# BSPD_Tester.net
KiCad netlist of a schematic drawn in EAGLE
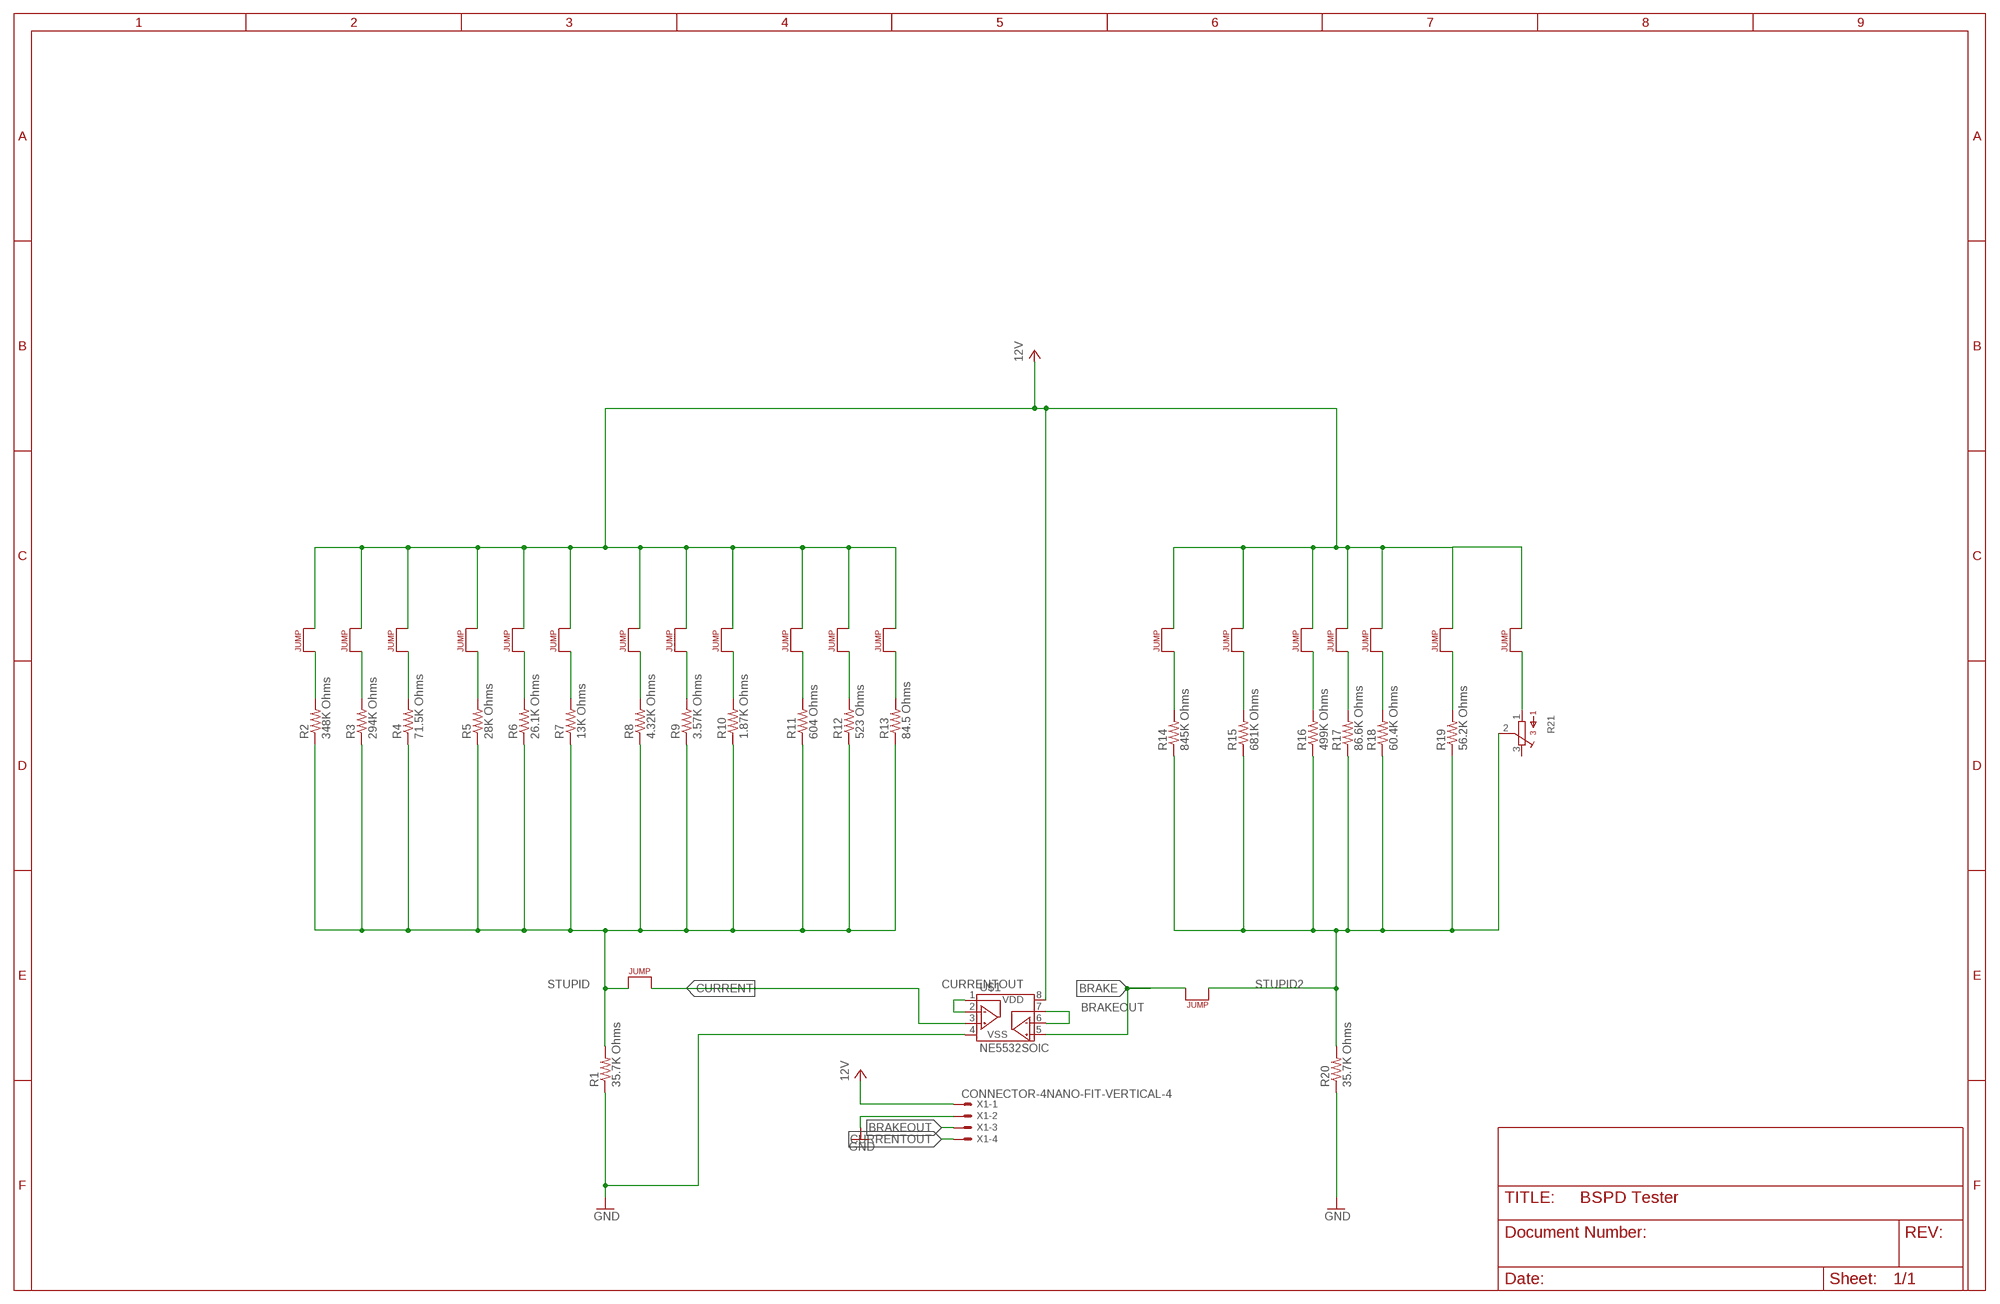
[diagram p0: schematic, sheet 1]

(export (version "E")
  (design (tool "Eeschema 10.0.6"))
  (components
    (comp (ref "J1")
      (value "JUMPER.1")
      (footprint "eagle-import:1X02")
      (libsource (lib "eagle-import") (part "JUMPER.1"))
    )
    (comp (ref "J2")
      (value "JUMPER.1")
      (footprint "eagle-import:1X02")
      (libsource (lib "eagle-import") (part "JUMPER.1"))
    )
    (comp (ref "J3")
      (value "JUMPER.1")
      (footprint "eagle-import:1X02")
      (libsource (lib "eagle-import") (part "JUMPER.1"))
    )
    (comp (ref "J4")
      (value "JUMPER.1")
      (footprint "eagle-import:1X02")
      (libsource (lib "eagle-import") (part "JUMPER.1"))
    )
    (comp (ref "J5")
      (value "JUMPER.1")
      (footprint "eagle-import:1X02")
      (libsource (lib "eagle-import") (part "JUMPER.1"))
    )
    (comp (ref "J6")
      (value "JUMPER.1")
      (footprint "eagle-import:1X02")
      (libsource (lib "eagle-import") (part "JUMPER.1"))
    )
    (comp (ref "J7")
      (value "JUMPER.1")
      (footprint "eagle-import:1X02")
      (libsource (lib "eagle-import") (part "JUMPER.1"))
    )
    (comp (ref "J8")
      (value "JUMPER.1")
      (footprint "eagle-import:1X02")
      (libsource (lib "eagle-import") (part "JUMPER.1"))
    )
    (comp (ref "J9")
      (value "JUMPER.1")
      (footprint "eagle-import:1X02")
      (libsource (lib "eagle-import") (part "JUMPER.1"))
    )
    (comp (ref "J10")
      (value "JUMPER.1")
      (footprint "eagle-import:1X02")
      (libsource (lib "eagle-import") (part "JUMPER.1"))
    )
    (comp (ref "J11")
      (value "JUMPER.1")
      (footprint "eagle-import:1X02")
      (libsource (lib "eagle-import") (part "JUMPER.1"))
    )
    (comp (ref "J12")
      (value "JUMPER.1")
      (footprint "eagle-import:1X02")
      (libsource (lib "eagle-import") (part "JUMPER.1"))
    )
    (comp (ref "J13")
      (value "JUMPER.1")
      (footprint "eagle-import:1X02")
      (libsource (lib "eagle-import") (part "JUMPER.1"))
    )
    (comp (ref "J14")
      (value "JUMPER.1")
      (footprint "eagle-import:1X02")
      (libsource (lib "eagle-import") (part "JUMPER.1"))
    )
    (comp (ref "J15")
      (value "JUMPER.1")
      (footprint "eagle-import:1X02")
      (libsource (lib "eagle-import") (part "JUMPER.1"))
    )
    (comp (ref "J16")
      (value "JUMPER.1")
      (footprint "eagle-import:1X02")
      (libsource (lib "eagle-import") (part "JUMPER.1"))
    )
    (comp (ref "J17")
      (value "JUMPER.1")
      (footprint "eagle-import:1X02")
      (libsource (lib "eagle-import") (part "JUMPER.1"))
    )
    (comp (ref "J18")
      (value "JUMPER.1")
      (footprint "eagle-import:1X02")
      (libsource (lib "eagle-import") (part "JUMPER.1"))
    )
    (comp (ref "J19")
      (value "JUMPER.1")
      (footprint "eagle-import:1X02")
      (libsource (lib "eagle-import") (part "JUMPER.1"))
    )
    (comp (ref "J20")
      (value "JUMPER.1")
      (footprint "eagle-import:1X02")
      (libsource (lib "eagle-import") (part "JUMPER.1"))
    )
    (comp (ref "J21")
      (value "JUMPER.1")
      (footprint "eagle-import:1X02")
      (libsource (lib "eagle-import") (part "JUMPER.1"))
    )
    (comp (ref "R1")
      (value "35.7K Ohms")
      (footprint "eagle-import:1206")
      (libsource (lib "eagle-import") (part "RESISTOR1206"))
    )
    (comp (ref "R2")
      (value "348K Ohms")
      (footprint "eagle-import:1206")
      (libsource (lib "eagle-import") (part "RESISTOR1206"))
    )
    (comp (ref "R3")
      (value "294K Ohms")
      (footprint "eagle-import:1206")
      (libsource (lib "eagle-import") (part "RESISTOR1206"))
    )
    (comp (ref "R4")
      (value "71.5K Ohms")
      (footprint "eagle-import:1206")
      (libsource (lib "eagle-import") (part "RESISTOR1206"))
    )
    (comp (ref "R5")
      (value "28K Ohms")
      (footprint "eagle-import:1206")
      (libsource (lib "eagle-import") (part "RESISTOR1206"))
    )
    (comp (ref "R6")
      (value "26.1K Ohms")
      (footprint "eagle-import:1206")
      (libsource (lib "eagle-import") (part "RESISTOR1206"))
    )
    (comp (ref "R7")
      (value "13K Ohms")
      (footprint "eagle-import:1206")
      (libsource (lib "eagle-import") (part "RESISTOR1206"))
    )
    (comp (ref "R8")
      (value "4.32K Ohms")
      (footprint "eagle-import:1206")
      (libsource (lib "eagle-import") (part "RESISTOR1206"))
    )
    (comp (ref "R9")
      (value "3.57K Ohms")
      (footprint "eagle-import:1206")
      (libsource (lib "eagle-import") (part "RESISTOR1206"))
    )
    (comp (ref "R10")
      (value "1.87K Ohms")
      (footprint "eagle-import:1206")
      (libsource (lib "eagle-import") (part "RESISTOR1206"))
    )
    (comp (ref "R11")
      (value "604 Ohms")
      (footprint "eagle-import:1206")
      (libsource (lib "eagle-import") (part "RESISTOR1206"))
    )
    (comp (ref "R12")
      (value "523 Ohms")
      (footprint "eagle-import:1206")
      (libsource (lib "eagle-import") (part "RESISTOR1206"))
    )
    (comp (ref "R13")
      (value "84.5 Ohms")
      (footprint "eagle-import:1206")
      (libsource (lib "eagle-import") (part "RESISTOR1206"))
    )
    (comp (ref "R14")
      (value "845K Ohms")
      (footprint "eagle-import:1206")
      (libsource (lib "eagle-import") (part "RESISTOR1206"))
    )
    (comp (ref "R15")
      (value "681K Ohms")
      (footprint "eagle-import:1206")
      (libsource (lib "eagle-import") (part "RESISTOR1206"))
    )
    (comp (ref "R16")
      (value "499K Ohms")
      (footprint "eagle-import:1206")
      (libsource (lib "eagle-import") (part "RESISTOR1206"))
    )
    (comp (ref "R17")
      (value "86.6K Ohms")
      (footprint "eagle-import:1206")
      (libsource (lib "eagle-import") (part "RESISTOR1206"))
    )
    (comp (ref "R18")
      (value "60.4K Ohms")
      (footprint "eagle-import:1206")
      (libsource (lib "eagle-import") (part "RESISTOR1206"))
    )
    (comp (ref "R19")
      (value "56.2K Ohms")
      (footprint "eagle-import:1206")
      (libsource (lib "eagle-import") (part "RESISTOR1206"))
    )
    (comp (ref "R20")
      (value "35.7K Ohms")
      (footprint "eagle-import:1206")
      (libsource (lib "eagle-import") (part "RESISTOR1206"))
    )
    (comp (ref "R21")
      (value "TRIMPOT_3296C")
      (footprint "eagle-import:TRIMPOT_3296")
      (libsource (lib "eagle-import") (part "TRIMPOT_3296C"))
    )
    (comp (ref "U$1")
      (value "NE5532SOIC")
      (footprint "eagle-import:SOIC-08")
      (libsource (lib "eagle-import") (part "NE5532SOIC"))
    )
    (comp (ref "X1")
      (value "CONNECTOR-4NANO-FIT-VERTICAL-4")
      (footprint "eagle-import:NANO-FIT_VERTICAL-4")
      (libsource (lib "eagle-import") (part "CONNECTOR-4NANO-FIT-VERTICAL-4"))
    )
  )
  (nets
    (net (code "1") (name "/STUPID") (class "Default")
      (node (ref "J19") (pin "1") (pinfunction "P$1_1") (pintype "bidirectional"))
      (node (ref "R1") (pin "2") (pinfunction "2_2") (pintype "passive"))
      (node (ref "R10") (pin "1") (pinfunction "1_1") (pintype "passive"))
      (node (ref "R11") (pin "1") (pinfunction "1_1") (pintype "passive"))
      (node (ref "R12") (pin "1") (pinfunction "1_1") (pintype "passive"))
      (node (ref "R13") (pin "1") (pinfunction "1_1") (pintype "passive"))
      (node (ref "R2") (pin "1") (pinfunction "1_1") (pintype "passive"))
      (node (ref "R3") (pin "1") (pinfunction "1_1") (pintype "passive"))
      (node (ref "R4") (pin "1") (pinfunction "1_1") (pintype "passive"))
      (node (ref "R5") (pin "1") (pinfunction "1_1") (pintype "passive"))
      (node (ref "R6") (pin "1") (pinfunction "1_1") (pintype "passive"))
      (node (ref "R7") (pin "1") (pinfunction "1_1") (pintype "passive"))
      (node (ref "R8") (pin "1") (pinfunction "1_1") (pintype "passive"))
      (node (ref "R9") (pin "1") (pinfunction "1_1") (pintype "passive"))
    )
    (net (code "2") (name "/STUPID2") (class "Default")
      (node (ref "J21") (pin "1") (pinfunction "P$1_1") (pintype "bidirectional"))
      (node (ref "R14") (pin "1") (pinfunction "1_1") (pintype "passive"))
      (node (ref "R15") (pin "1") (pinfunction "1_1") (pintype "passive"))
      (node (ref "R16") (pin "1") (pinfunction "1_1") (pintype "passive"))
      (node (ref "R17") (pin "1") (pinfunction "1_1") (pintype "passive"))
      (node (ref "R18") (pin "1") (pinfunction "1_1") (pintype "passive"))
      (node (ref "R19") (pin "1") (pinfunction "1_1") (pintype "passive"))
      (node (ref "R20") (pin "2") (pinfunction "2_2") (pintype "passive"))
      (node (ref "R21") (pin "2") (pinfunction "2_2") (pintype "passive"))
    )
    (net (code "3") (name "12V") (class "Default")
      (node (ref "J1") (pin "2") (pinfunction "P$2_2") (pintype "bidirectional"))
      (node (ref "J10") (pin "2") (pinfunction "P$2_2") (pintype "bidirectional"))
      (node (ref "J11") (pin "2") (pinfunction "P$2_2") (pintype "bidirectional"))
      (node (ref "J12") (pin "2") (pinfunction "P$2_2") (pintype "bidirectional"))
      (node (ref "J13") (pin "2") (pinfunction "P$2_2") (pintype "bidirectional"))
      (node (ref "J14") (pin "2") (pinfunction "P$2_2") (pintype "bidirectional"))
      (node (ref "J15") (pin "2") (pinfunction "P$2_2") (pintype "bidirectional"))
      (node (ref "J16") (pin "2") (pinfunction "P$2_2") (pintype "bidirectional"))
      (node (ref "J17") (pin "2") (pinfunction "P$2_2") (pintype "bidirectional"))
      (node (ref "J18") (pin "2") (pinfunction "P$2_2") (pintype "bidirectional"))
      (node (ref "J2") (pin "2") (pinfunction "P$2_2") (pintype "bidirectional"))
      (node (ref "J20") (pin "2") (pinfunction "P$2_2") (pintype "bidirectional"))
      (node (ref "J3") (pin "2") (pinfunction "P$2_2") (pintype "bidirectional"))
      (node (ref "J4") (pin "2") (pinfunction "P$2_2") (pintype "bidirectional"))
      (node (ref "J5") (pin "2") (pinfunction "P$2_2") (pintype "bidirectional"))
      (node (ref "J6") (pin "2") (pinfunction "P$2_2") (pintype "bidirectional"))
      (node (ref "J7") (pin "2") (pinfunction "P$2_2") (pintype "bidirectional"))
      (node (ref "J8") (pin "2") (pinfunction "P$2_2") (pintype "bidirectional"))
      (node (ref "J9") (pin "2") (pinfunction "P$2_2") (pintype "bidirectional"))
      (node (ref "U$1") (pin "8") (pinfunction "VDD_8") (pintype "passive"))
      (node (ref "X1") (pin "P$1") (pinfunction "S_P$1") (pintype "passive"))
    )
    (net (code "4") (name "BRAKE") (class "Default")
      (node (ref "J21") (pin "2") (pinfunction "P$2_2") (pintype "bidirectional"))
      (node (ref "U$1") (pin "5") (pinfunction "VINB+_5") (pintype "passive"))
    )
    (net (code "5") (name "BRAKEOUT") (class "Default")
      (node (ref "U$1") (pin "6") (pinfunction "VINB-_6") (pintype "passive"))
      (node (ref "U$1") (pin "7") (pinfunction "VOUTB_7") (pintype "passive"))
      (node (ref "X1") (pin "P$3") (pinfunction "S_P$3") (pintype "passive"))
    )
    (net (code "6") (name "CURRENT") (class "Default")
      (node (ref "J19") (pin "2") (pinfunction "P$2_2") (pintype "bidirectional"))
      (node (ref "U$1") (pin "3") (pinfunction "VINA+_3") (pintype "passive"))
    )
    (net (code "7") (name "CURRENTOUT") (class "Default")
      (node (ref "U$1") (pin "1") (pinfunction "VOUTA_1") (pintype "passive"))
      (node (ref "U$1") (pin "2") (pinfunction "VINA-_2") (pintype "passive"))
      (node (ref "X1") (pin "P$4") (pinfunction "S_P$4") (pintype "passive"))
    )
    (net (code "8") (name "GND") (class "Default")
      (node (ref "R1") (pin "1") (pinfunction "1_1") (pintype "passive"))
      (node (ref "R20") (pin "1") (pinfunction "1_1") (pintype "passive"))
      (node (ref "U$1") (pin "4") (pinfunction "VSS_4") (pintype "passive"))
      (node (ref "X1") (pin "P$2") (pinfunction "S_P$2") (pintype "passive"))
    )
    (net (code "9") (name "Net-(J1-P$1)") (class "Default")
      (node (ref "J1") (pin "1") (pinfunction "P$1_1") (pintype "bidirectional"))
      (node (ref "R2") (pin "2") (pinfunction "2_2") (pintype "passive"))
    )
    (net (code "10") (name "Net-(J2-P$1)") (class "Default")
      (node (ref "J2") (pin "1") (pinfunction "P$1_1") (pintype "bidirectional"))
      (node (ref "R3") (pin "2") (pinfunction "2_2") (pintype "passive"))
    )
    (net (code "11") (name "Net-(J3-P$1)") (class "Default")
      (node (ref "J3") (pin "1") (pinfunction "P$1_1") (pintype "bidirectional"))
      (node (ref "R4") (pin "2") (pinfunction "2_2") (pintype "passive"))
    )
    (net (code "12") (name "Net-(J4-P$1)") (class "Default")
      (node (ref "J4") (pin "1") (pinfunction "P$1_1") (pintype "bidirectional"))
      (node (ref "R5") (pin "2") (pinfunction "2_2") (pintype "passive"))
    )
    (net (code "13") (name "Net-(J5-P$1)") (class "Default")
      (node (ref "J5") (pin "1") (pinfunction "P$1_1") (pintype "bidirectional"))
      (node (ref "R6") (pin "2") (pinfunction "2_2") (pintype "passive"))
    )
    (net (code "14") (name "Net-(J6-P$1)") (class "Default")
      (node (ref "J6") (pin "1") (pinfunction "P$1_1") (pintype "bidirectional"))
      (node (ref "R7") (pin "2") (pinfunction "2_2") (pintype "passive"))
    )
    (net (code "15") (name "Net-(J7-P$1)") (class "Default")
      (node (ref "J7") (pin "1") (pinfunction "P$1_1") (pintype "bidirectional"))
      (node (ref "R8") (pin "2") (pinfunction "2_2") (pintype "passive"))
    )
    (net (code "16") (name "Net-(J8-P$1)") (class "Default")
      (node (ref "J8") (pin "1") (pinfunction "P$1_1") (pintype "bidirectional"))
      (node (ref "R9") (pin "2") (pinfunction "2_2") (pintype "passive"))
    )
    (net (code "17") (name "Net-(J9-P$1)") (class "Default")
      (node (ref "J9") (pin "1") (pinfunction "P$1_1") (pintype "bidirectional"))
      (node (ref "R10") (pin "2") (pinfunction "2_2") (pintype "passive"))
    )
    (net (code "18") (name "Net-(J10-P$1)") (class "Default")
      (node (ref "J10") (pin "1") (pinfunction "P$1_1") (pintype "bidirectional"))
      (node (ref "R11") (pin "2") (pinfunction "2_2") (pintype "passive"))
    )
    (net (code "19") (name "Net-(J11-P$1)") (class "Default")
      (node (ref "J11") (pin "1") (pinfunction "P$1_1") (pintype "bidirectional"))
      (node (ref "R12") (pin "2") (pinfunction "2_2") (pintype "passive"))
    )
    (net (code "20") (name "Net-(J12-P$1)") (class "Default")
      (node (ref "J12") (pin "1") (pinfunction "P$1_1") (pintype "bidirectional"))
      (node (ref "R13") (pin "2") (pinfunction "2_2") (pintype "passive"))
    )
    (net (code "21") (name "Net-(J13-P$1)") (class "Default")
      (node (ref "J13") (pin "1") (pinfunction "P$1_1") (pintype "bidirectional"))
      (node (ref "R14") (pin "2") (pinfunction "2_2") (pintype "passive"))
    )
    (net (code "22") (name "Net-(J14-P$1)") (class "Default")
      (node (ref "J14") (pin "1") (pinfunction "P$1_1") (pintype "bidirectional"))
      (node (ref "R15") (pin "2") (pinfunction "2_2") (pintype "passive"))
    )
    (net (code "23") (name "Net-(J15-P$1)") (class "Default")
      (node (ref "J15") (pin "1") (pinfunction "P$1_1") (pintype "bidirectional"))
      (node (ref "R16") (pin "2") (pinfunction "2_2") (pintype "passive"))
    )
    (net (code "24") (name "Net-(J16-P$1)") (class "Default")
      (node (ref "J16") (pin "1") (pinfunction "P$1_1") (pintype "bidirectional"))
      (node (ref "R17") (pin "2") (pinfunction "2_2") (pintype "passive"))
    )
    (net (code "25") (name "Net-(J17-P$1)") (class "Default")
      (node (ref "J17") (pin "1") (pinfunction "P$1_1") (pintype "bidirectional"))
      (node (ref "R18") (pin "2") (pinfunction "2_2") (pintype "passive"))
    )
    (net (code "26") (name "Net-(J18-P$1)") (class "Default")
      (node (ref "J18") (pin "1") (pinfunction "P$1_1") (pintype "bidirectional"))
      (node (ref "R19") (pin "2") (pinfunction "2_2") (pintype "passive"))
    )
    (net (code "27") (name "Net-(J20-P$1)") (class "Default")
      (node (ref "J20") (pin "1") (pinfunction "P$1_1") (pintype "bidirectional"))
      (node (ref "R21") (pin "1") (pinfunction "1_1") (pintype "passive"))
    )
    (net (code "28") (name "unconnected-(R21-Pad3)") (class "Default")
      (node (ref "R21") (pin "3") (pinfunction "3_3") (pintype "passive"))
    )
  )
)
